# pcb1e.net
KiCad netlist of a schematic drawn in EAGLE
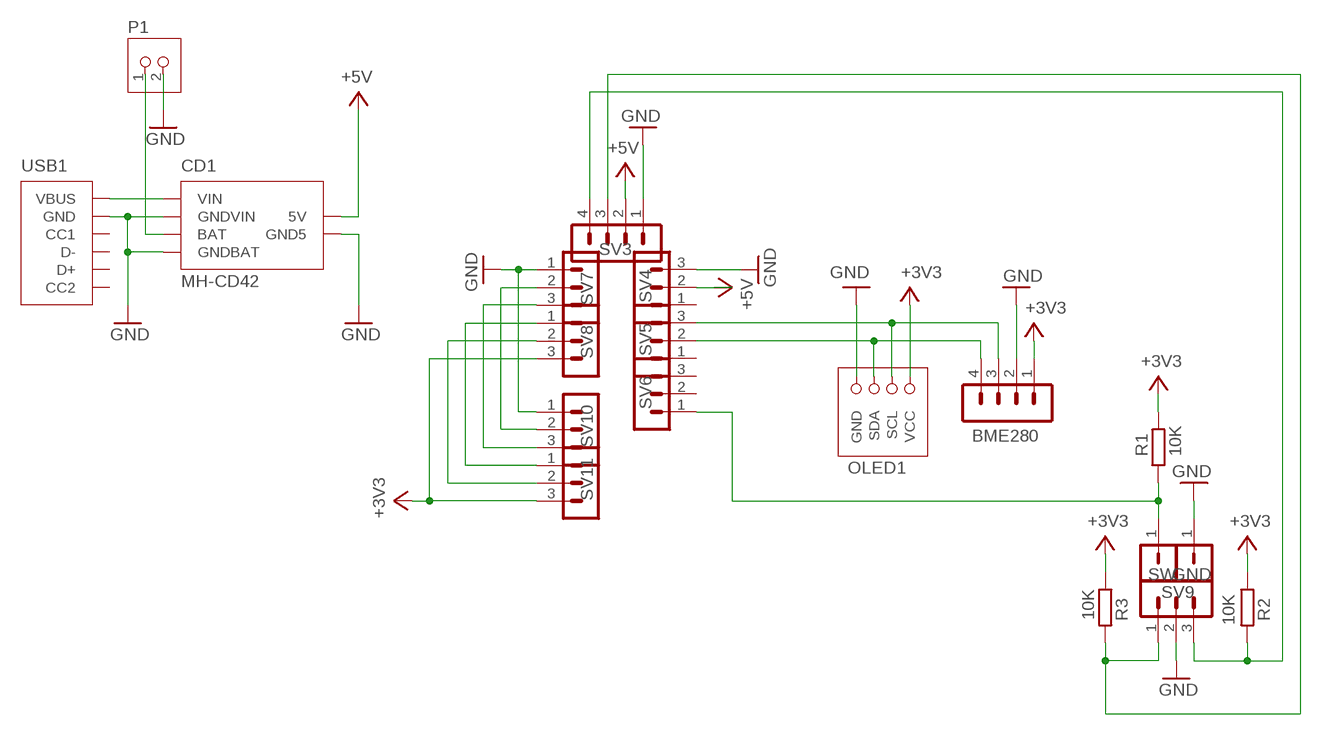
[diagram p0: schematic, sheet 1]

(export (version "E")
  (design (tool "Eeschema 10.0.6"))
  (components
    (comp (ref "BME280")
      (value "PINHEAD-MA04-1")
      (footprint "eagle-import:PINHEAD-MA04-1")
      (libsource (lib "eagle-import") (part "PINHEAD-MA04-1"))
    )
    (comp (ref "CD1")
      (value "MH-CD42")
      (footprint "eagle-import:MH-CD42")
      (libsource (lib "eagle-import") (part "MH-CD42"))
    )
    (comp (ref "GND")
      (value "PINHEAD-MA01-1")
      (footprint "eagle-import:PINHEAD-MA01-1")
      (libsource (lib "eagle-import") (part "PINHEAD-MA01-1"))
    )
    (comp (ref "OLED1")
      (value "OLED-SSD1306-0.96")
      (footprint "eagle-import:OLED-I2C-0.96")
      (libsource (lib "eagle-import") (part "OLED-SSD1306-0.96"))
    )
    (comp (ref "P1")
      (value "JST-PH2")
      (footprint "eagle-import:JST-PH2")
      (libsource (lib "eagle-import") (part "JST-PH2"))
    )
    (comp (ref "R1")
      (value "10K")
      (footprint "eagle-import:0204_5")
      (libsource (lib "eagle-import") (part "R-EU_0204/5"))
    )
    (comp (ref "R2")
      (value "10K")
      (footprint "eagle-import:0204_5")
      (libsource (lib "eagle-import") (part "R-EU_0204/5"))
    )
    (comp (ref "R3")
      (value "10K")
      (footprint "eagle-import:0204_5")
      (libsource (lib "eagle-import") (part "R-EU_0204/5"))
    )
    (comp (ref "SV3")
      (value "PINHEAD-MA04-1")
      (footprint "eagle-import:PINHEAD-MA04-1")
      (libsource (lib "eagle-import") (part "PINHEAD-MA04-1"))
    )
    (comp (ref "SV4")
      (value "PINHEAD-MA03-1")
      (footprint "eagle-import:PINHEAD-MA03-1")
      (libsource (lib "eagle-import") (part "PINHEAD-MA03-1"))
    )
    (comp (ref "SV5")
      (value "PINHEAD-MA03-1")
      (footprint "eagle-import:PINHEAD-MA03-1")
      (libsource (lib "eagle-import") (part "PINHEAD-MA03-1"))
    )
    (comp (ref "SV6")
      (value "PINHEAD-MA03-1")
      (footprint "eagle-import:PINHEAD-MA03-1")
      (libsource (lib "eagle-import") (part "PINHEAD-MA03-1"))
    )
    (comp (ref "SV7")
      (value "PINHEAD-MA03-1")
      (footprint "eagle-import:PINHEAD-MA03-1")
      (libsource (lib "eagle-import") (part "PINHEAD-MA03-1"))
    )
    (comp (ref "SV8")
      (value "PINHEAD-MA03-1")
      (footprint "eagle-import:PINHEAD-MA03-1")
      (libsource (lib "eagle-import") (part "PINHEAD-MA03-1"))
    )
    (comp (ref "SV9")
      (value "PINHEAD-MA03-1")
      (footprint "eagle-import:PINHEAD-MA03-1")
      (libsource (lib "eagle-import") (part "PINHEAD-MA03-1"))
    )
    (comp (ref "SV10")
      (value "PINHEAD-MA03-1")
      (footprint "eagle-import:PINHEAD-MA03-1")
      (libsource (lib "eagle-import") (part "PINHEAD-MA03-1"))
    )
    (comp (ref "SV11")
      (value "PINHEAD-MA03-1")
      (footprint "eagle-import:PINHEAD-MA03-1")
      (libsource (lib "eagle-import") (part "PINHEAD-MA03-1"))
    )
    (comp (ref "SW")
      (value "PINHEAD-MA01-1")
      (footprint "eagle-import:PINHEAD-MA01-1")
      (libsource (lib "eagle-import") (part "PINHEAD-MA01-1"))
    )
    (comp (ref "USB1")
      (value "USB-C-DIRECT")
      (footprint "eagle-import:USB-C-DIRECT")
      (libsource (lib "eagle-import") (part "USB-C-DIRECT"))
    )
  )
  (nets
    (net (code "1") (name "+3V3") (class "Default")
      (node (ref "BME280") (pin "1") (pinfunction "1_1") (pintype "passive"))
      (node (ref "OLED1") (pin "VCC") (pinfunction "VCC_VCC") (pintype "bidirectional"))
      (node (ref "R1") (pin "2") (pinfunction "2_2") (pintype "passive"))
      (node (ref "R2") (pin "1") (pinfunction "1_1") (pintype "passive"))
      (node (ref "R3") (pin "1") (pinfunction "1_1") (pintype "passive"))
      (node (ref "SV11") (pin "3") (pinfunction "3_3") (pintype "passive"))
      (node (ref "SV8") (pin "3") (pinfunction "3_3") (pintype "passive"))
    )
    (net (code "2") (name "+5V") (class "Default")
      (node (ref "CD1") (pin "5V") (pinfunction "5V_5V") (pintype "bidirectional"))
      (node (ref "SV3") (pin "2") (pinfunction "2_2") (pintype "passive"))
      (node (ref "SV4") (pin "2") (pinfunction "2_2") (pintype "passive"))
    )
    (net (code "3") (name "GND") (class "Default")
      (node (ref "BME280") (pin "2") (pinfunction "2_2") (pintype "passive"))
      (node (ref "CD1") (pin "GND5V") (pinfunction "GND5_GND5V") (pintype "bidirectional"))
      (node (ref "CD1") (pin "GNDBAT") (pinfunction "GNDBAT_GNDBAT") (pintype "bidirectional"))
      (node (ref "CD1") (pin "GNDVIN") (pinfunction "GNDVIN_GNDVIN") (pintype "bidirectional"))
      (node (ref "GND") (pin "1") (pinfunction "1_1") (pintype "passive"))
      (node (ref "OLED1") (pin "GND") (pinfunction "GND_GND") (pintype "bidirectional"))
      (node (ref "P1") (pin "2") (pinfunction "2_2") (pintype "passive"))
      (node (ref "SV10") (pin "1") (pinfunction "1_1") (pintype "passive"))
      (node (ref "SV3") (pin "1") (pinfunction "1_1") (pintype "passive"))
      (node (ref "SV4") (pin "3") (pinfunction "3_3") (pintype "passive"))
      (node (ref "SV7") (pin "1") (pinfunction "1_1") (pintype "passive"))
      (node (ref "SV9") (pin "2") (pinfunction "2_2") (pintype "passive"))
      (node (ref "USB1") (pin "GND") (pinfunction "GND_GND") (pintype "bidirectional"))
    )
    (net (code "4") (name "Net-(BME280-Pad3)") (class "Default")
      (node (ref "BME280") (pin "3") (pinfunction "3_3") (pintype "passive"))
      (node (ref "OLED1") (pin "SCL") (pinfunction "SCL_SCL") (pintype "bidirectional"))
      (node (ref "SV5") (pin "3") (pinfunction "3_3") (pintype "passive"))
    )
    (net (code "5") (name "Net-(BME280-Pad4)") (class "Default")
      (node (ref "BME280") (pin "4") (pinfunction "4_4") (pintype "passive"))
      (node (ref "OLED1") (pin "SDA") (pinfunction "SDA_SDA") (pintype "bidirectional"))
      (node (ref "SV5") (pin "2") (pinfunction "2_2") (pintype "passive"))
    )
    (net (code "6") (name "Net-(CD1-PadBAT)") (class "Default")
      (node (ref "CD1") (pin "BAT") (pinfunction "BAT_BAT") (pintype "bidirectional"))
      (node (ref "P1") (pin "1") (pinfunction "1_1") (pintype "passive"))
    )
    (net (code "7") (name "Net-(CD1-PadVIN)") (class "Default")
      (node (ref "CD1") (pin "VIN") (pinfunction "VIN_VIN") (pintype "bidirectional"))
      (node (ref "USB1") (pin "VBUS") (pinfunction "VBUS_VBUS") (pintype "bidirectional"))
    )
    (net (code "8") (name "Net-(R1-Pad1)") (class "Default")
      (node (ref "R1") (pin "1") (pinfunction "1_1") (pintype "passive"))
      (node (ref "SV6") (pin "1") (pinfunction "1_1") (pintype "passive"))
      (node (ref "SW") (pin "1") (pinfunction "1_1") (pintype "passive"))
    )
    (net (code "9") (name "Net-(R2-Pad2)") (class "Default")
      (node (ref "R2") (pin "2") (pinfunction "2_2") (pintype "passive"))
      (node (ref "SV3") (pin "4") (pinfunction "4_4") (pintype "passive"))
      (node (ref "SV9") (pin "3") (pinfunction "3_3") (pintype "passive"))
    )
    (net (code "10") (name "Net-(R3-Pad2)") (class "Default")
      (node (ref "R3") (pin "2") (pinfunction "2_2") (pintype "passive"))
      (node (ref "SV3") (pin "3") (pinfunction "3_3") (pintype "passive"))
      (node (ref "SV9") (pin "1") (pinfunction "1_1") (pintype "passive"))
    )
    (net (code "11") (name "Net-(SV10-Pad2)") (class "Default")
      (node (ref "SV10") (pin "2") (pinfunction "2_2") (pintype "passive"))
      (node (ref "SV7") (pin "2") (pinfunction "2_2") (pintype "passive"))
    )
    (net (code "12") (name "Net-(SV10-Pad3)") (class "Default")
      (node (ref "SV10") (pin "3") (pinfunction "3_3") (pintype "passive"))
      (node (ref "SV7") (pin "3") (pinfunction "3_3") (pintype "passive"))
    )
    (net (code "13") (name "Net-(SV11-Pad1)") (class "Default")
      (node (ref "SV11") (pin "1") (pinfunction "1_1") (pintype "passive"))
      (node (ref "SV8") (pin "1") (pinfunction "1_1") (pintype "passive"))
    )
    (net (code "14") (name "Net-(SV11-Pad2)") (class "Default")
      (node (ref "SV11") (pin "2") (pinfunction "2_2") (pintype "passive"))
      (node (ref "SV8") (pin "2") (pinfunction "2_2") (pintype "passive"))
    )
    (net (code "15") (name "unconnected-(SV4-Pad1)") (class "Default")
      (node (ref "SV4") (pin "1") (pinfunction "1_1") (pintype "passive"))
    )
    (net (code "16") (name "unconnected-(SV5-Pad1)") (class "Default")
      (node (ref "SV5") (pin "1") (pinfunction "1_1") (pintype "passive"))
    )
    (net (code "17") (name "unconnected-(SV6-Pad2)") (class "Default")
      (node (ref "SV6") (pin "2") (pinfunction "2_2") (pintype "passive"))
    )
    (net (code "18") (name "unconnected-(SV6-Pad3)") (class "Default")
      (node (ref "SV6") (pin "3") (pinfunction "3_3") (pintype "passive"))
    )
    (net (code "19") (name "unconnected-(USB1-PadCC1)") (class "Default")
      (node (ref "USB1") (pin "CC1") (pinfunction "CC1_CC1") (pintype "bidirectional"))
    )
    (net (code "20") (name "unconnected-(USB1-PadCC2)") (class "Default")
      (node (ref "USB1") (pin "CC2") (pinfunction "CC2_CC2") (pintype "bidirectional"))
    )
    (net (code "21") (name "unconnected-(USB1-PadD+)") (class "Default")
      (node (ref "USB1") (pin "D+") (pinfunction "D+_D+") (pintype "bidirectional"))
    )
    (net (code "22") (name "unconnected-(USB1-PadD-)") (class "Default")
      (node (ref "USB1") (pin "D-") (pinfunction "D-_D-") (pintype "bidirectional"))
    )
  )
)
